# Ethernet.net
KiCad netlist of a schematic drawn in Altium Designer
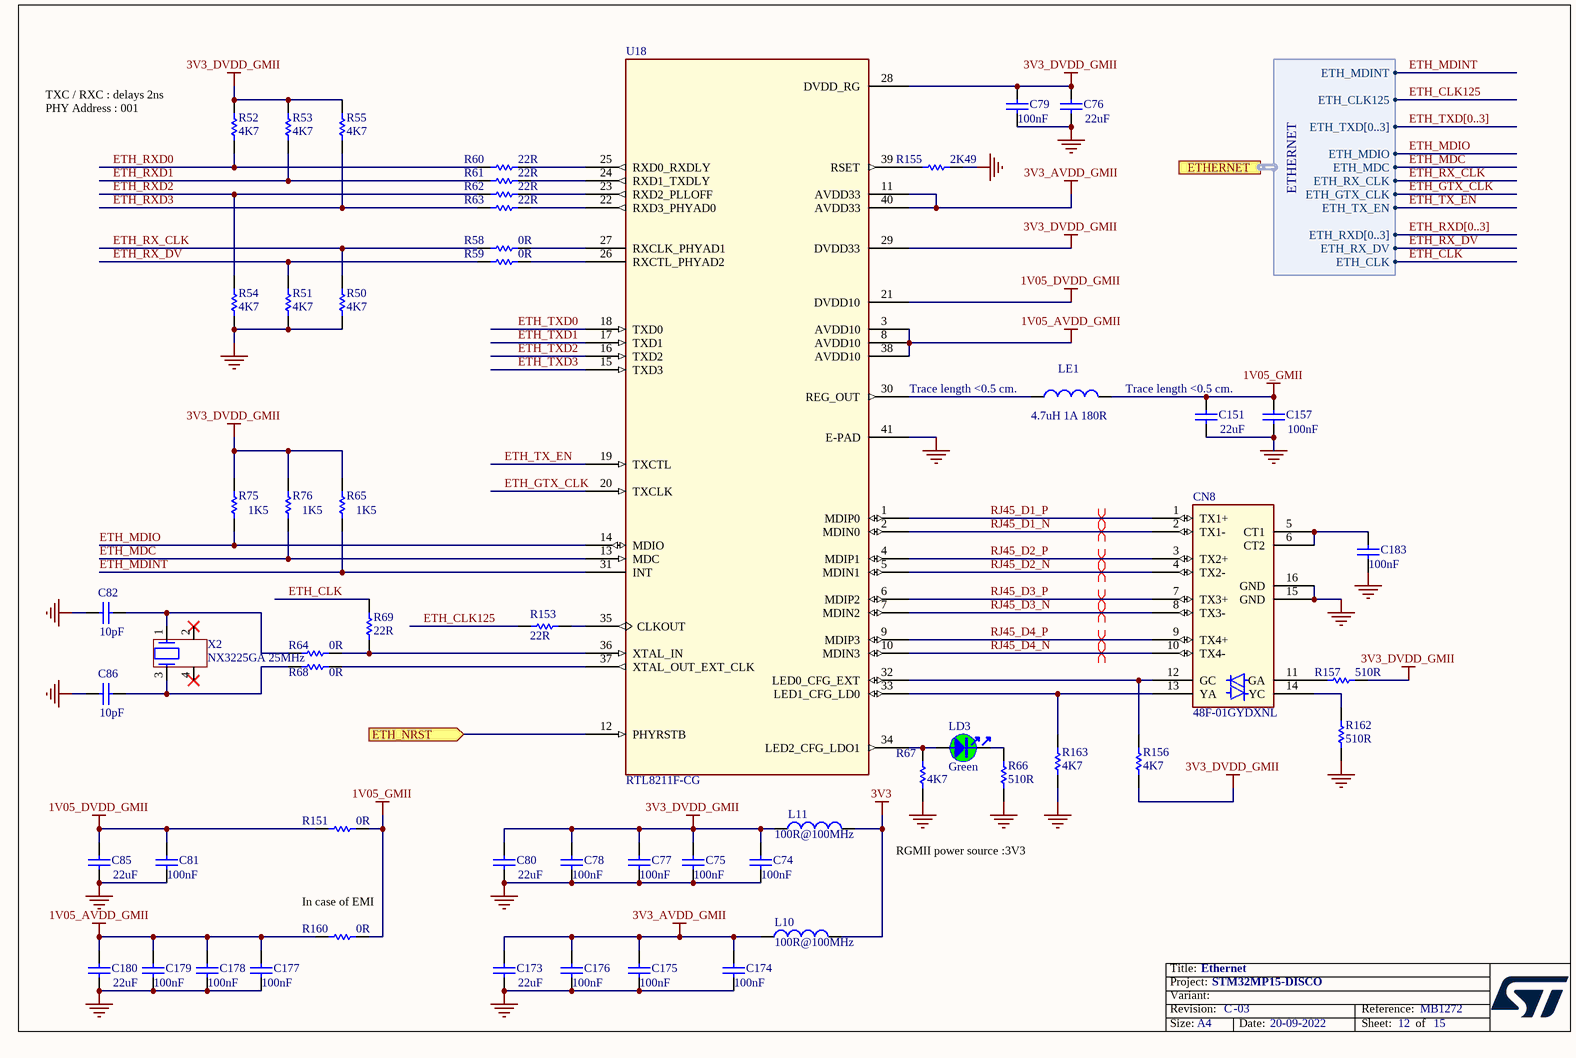
[diagram p0: Ethernet.SchDoc]

(export (version "E")
  (design (tool "Eeschema 10.0.6"))
  (components
    (comp (ref "C74")
      (value "100nF")
      (footprint "C0402")
      (description "Capacitor,100nF,16V,X7R,10%,0402")
      (fields
        (field (name "INTERNAL_PART_NUMBER") "MCD-00006")
        (field (name "MANUFACTURER_PART_NUMBER") "CC0402KRX7R7BB104")
        (field (name "PROVIDED_BY") "SUBCO")
      )
      (libsource (lib "MCD_PARTS_database") (part "Capacitor"))
    )
    (comp (ref "C75")
      (value "100nF")
      (footprint "C0402")
      (description "Capacitor,100nF,16V,X7R,10%,0402")
      (fields
        (field (name "INTERNAL_PART_NUMBER") "MCD-00006")
        (field (name "MANUFACTURER_PART_NUMBER") "CC0402KRX7R7BB104")
        (field (name "PROVIDED_BY") "SUBCO")
      )
      (libsource (lib "MCD_PARTS_database") (part "Capacitor"))
    )
    (comp (ref "C76")
      (value "22uF")
      (footprint "C0603")
      (description "Capacitor,22uF,6V3,X5R,20%,0603")
      (fields
        (field (name "INTERNAL_PART_NUMBER") "MCD-00100")
        (field (name "MANUFACTURER_PART_NUMBER") "GRM188R60J226MEA0J")
        (field (name "PROVIDED_BY") "SUBCO")
      )
      (libsource (lib "MCD_PARTS_database") (part "Capacitor"))
    )
    (comp (ref "C77")
      (value "100nF")
      (footprint "C0402")
      (description "Capacitor,100nF,16V,X7R,10%,0402")
      (fields
        (field (name "INTERNAL_PART_NUMBER") "MCD-00006")
        (field (name "MANUFACTURER_PART_NUMBER") "CC0402KRX7R7BB104")
        (field (name "PROVIDED_BY") "SUBCO")
      )
      (libsource (lib "MCD_PARTS_database") (part "Capacitor"))
    )
    (comp (ref "C78")
      (value "100nF")
      (footprint "C0402")
      (description "Capacitor,100nF,16V,X7R,10%,0402")
      (fields
        (field (name "INTERNAL_PART_NUMBER") "MCD-00006")
        (field (name "MANUFACTURER_PART_NUMBER") "CC0402KRX7R7BB104")
        (field (name "PROVIDED_BY") "SUBCO")
      )
      (libsource (lib "MCD_PARTS_database") (part "Capacitor"))
    )
    (comp (ref "C79")
      (value "100nF")
      (footprint "C0402")
      (description "Capacitor,100nF,16V,X7R,10%,0402")
      (fields
        (field (name "INTERNAL_PART_NUMBER") "MCD-00006")
        (field (name "MANUFACTURER_PART_NUMBER") "CC0402KRX7R7BB104")
        (field (name "PROVIDED_BY") "SUBCO")
      )
      (libsource (lib "MCD_PARTS_database") (part "Capacitor"))
    )
    (comp (ref "C80")
      (value "22uF")
      (footprint "C0603")
      (description "Capacitor,22uF,6V3,X5R,20%,0603")
      (fields
        (field (name "INTERNAL_PART_NUMBER") "MCD-00100")
        (field (name "MANUFACTURER_PART_NUMBER") "GRM188R60J226MEA0J")
        (field (name "PROVIDED_BY") "SUBCO")
      )
      (libsource (lib "MCD_PARTS_database") (part "Capacitor"))
    )
    (comp (ref "C81")
      (value "100nF")
      (footprint "C0402")
      (description "Capacitor,100nF,16V,X7R,10%,0402")
      (fields
        (field (name "INTERNAL_PART_NUMBER") "MCD-00006")
        (field (name "MANUFACTURER_PART_NUMBER") "CC0402KRX7R7BB104")
        (field (name "PROVIDED_BY") "SUBCO")
      )
      (libsource (lib "MCD_PARTS_database") (part "Capacitor"))
    )
    (comp (ref "C82")
      (value "10pF")
      (footprint "C0402")
      (description "Capacitor,10pF,50V,NPO,5%,0402")
      (fields
        (field (name "INTERNAL_PART_NUMBER") "MCD-00015")
        (field (name "MANUFACTURER_PART_NUMBER") "CC0402JRNPO9BN100")
        (field (name "PROVIDED_BY") "SUBCO")
      )
      (libsource (lib "MCD_PARTS_database") (part "Capacitor"))
    )
    (comp (ref "C85")
      (value "22uF")
      (footprint "C0603")
      (description "Capacitor,22uF,6V3,X5R,20%,0603")
      (fields
        (field (name "INTERNAL_PART_NUMBER") "MCD-00100")
        (field (name "MANUFACTURER_PART_NUMBER") "GRM188R60J226MEA0J")
        (field (name "PROVIDED_BY") "SUBCO")
      )
      (libsource (lib "MCD_PARTS_database") (part "Capacitor"))
    )
    (comp (ref "C86")
      (value "10pF")
      (footprint "C0402")
      (description "Capacitor,10pF,50V,NPO,5%,0402")
      (fields
        (field (name "INTERNAL_PART_NUMBER") "MCD-00015")
        (field (name "MANUFACTURER_PART_NUMBER") "CC0402JRNPO9BN100")
        (field (name "PROVIDED_BY") "SUBCO")
      )
      (libsource (lib "MCD_PARTS_database") (part "Capacitor"))
    )
    (comp (ref "C151")
      (value "22uF")
      (footprint "C0603")
      (description "Capacitor,22uF,6V3,X5R,20%,0603")
      (fields
        (field (name "INTERNAL_PART_NUMBER") "MCD-00100")
        (field (name "MANUFACTURER_PART_NUMBER") "GRM188R60J226MEA0J")
        (field (name "PROVIDED_BY") "SUBCO")
      )
      (libsource (lib "MCD_PARTS_database") (part "Capacitor"))
    )
    (comp (ref "C157")
      (value "100nF")
      (footprint "C0402")
      (description "Capacitor,100nF,16V,X7R,10%,0402")
      (fields
        (field (name "INTERNAL_PART_NUMBER") "MCD-00006")
        (field (name "MANUFACTURER_PART_NUMBER") "CC0402KRX7R7BB104")
        (field (name "PROVIDED_BY") "SUBCO")
      )
      (libsource (lib "MCD_PARTS_database") (part "Capacitor"))
    )
    (comp (ref "C173")
      (value "22uF")
      (footprint "C0603")
      (description "Capacitor,22uF,6V3,X5R,20%,0603")
      (fields
        (field (name "INTERNAL_PART_NUMBER") "MCD-00100")
        (field (name "MANUFACTURER_PART_NUMBER") "GRM188R60J226MEA0J")
        (field (name "PROVIDED_BY") "SUBCO")
      )
      (libsource (lib "MCD_PARTS_database") (part "Capacitor"))
    )
    (comp (ref "C174")
      (value "100nF")
      (footprint "C0402")
      (description "Capacitor,100nF,16V,X7R,10%,0402")
      (fields
        (field (name "INTERNAL_PART_NUMBER") "MCD-00006")
        (field (name "MANUFACTURER_PART_NUMBER") "CC0402KRX7R7BB104")
        (field (name "PROVIDED_BY") "SUBCO")
      )
      (libsource (lib "MCD_PARTS_database") (part "Capacitor"))
    )
    (comp (ref "C175")
      (value "100nF")
      (footprint "C0402")
      (description "Capacitor,100nF,16V,X7R,10%,0402")
      (fields
        (field (name "INTERNAL_PART_NUMBER") "MCD-00006")
        (field (name "MANUFACTURER_PART_NUMBER") "CC0402KRX7R7BB104")
        (field (name "PROVIDED_BY") "SUBCO")
      )
      (libsource (lib "MCD_PARTS_database") (part "Capacitor"))
    )
    (comp (ref "C176")
      (value "100nF")
      (footprint "C0402")
      (description "Capacitor,100nF,16V,X7R,10%,0402")
      (fields
        (field (name "INTERNAL_PART_NUMBER") "MCD-00006")
        (field (name "MANUFACTURER_PART_NUMBER") "CC0402KRX7R7BB104")
        (field (name "PROVIDED_BY") "SUBCO")
      )
      (libsource (lib "MCD_PARTS_database") (part "Capacitor"))
    )
    (comp (ref "C177")
      (value "100nF")
      (footprint "C0402")
      (description "Capacitor,100nF,16V,X7R,10%,0402")
      (fields
        (field (name "INTERNAL_PART_NUMBER") "MCD-00006")
        (field (name "MANUFACTURER_PART_NUMBER") "CC0402KRX7R7BB104")
        (field (name "PROVIDED_BY") "SUBCO")
      )
      (libsource (lib "MCD_PARTS_database") (part "Capacitor"))
    )
    (comp (ref "C178")
      (value "100nF")
      (footprint "C0402")
      (description "Capacitor,100nF,16V,X7R,10%,0402")
      (fields
        (field (name "INTERNAL_PART_NUMBER") "MCD-00006")
        (field (name "MANUFACTURER_PART_NUMBER") "CC0402KRX7R7BB104")
        (field (name "PROVIDED_BY") "SUBCO")
      )
      (libsource (lib "MCD_PARTS_database") (part "Capacitor"))
    )
    (comp (ref "C179")
      (value "100nF")
      (footprint "C0402")
      (description "Capacitor,100nF,16V,X7R,10%,0402")
      (fields
        (field (name "INTERNAL_PART_NUMBER") "MCD-00006")
        (field (name "MANUFACTURER_PART_NUMBER") "CC0402KRX7R7BB104")
        (field (name "PROVIDED_BY") "SUBCO")
      )
      (libsource (lib "MCD_PARTS_database") (part "Capacitor"))
    )
    (comp (ref "C180")
      (value "22uF")
      (footprint "C0603")
      (description "Capacitor,22uF,6V3,X5R,20%,0603")
      (fields
        (field (name "INTERNAL_PART_NUMBER") "MCD-00100")
        (field (name "MANUFACTURER_PART_NUMBER") "GRM188R60J226MEA0J")
        (field (name "PROVIDED_BY") "SUBCO")
      )
      (libsource (lib "MCD_PARTS_database") (part "Capacitor"))
    )
    (comp (ref "C183")
      (value "100nF")
      (footprint "C0402")
      (description "Capacitor,100nF,16V,X7R,10%,0402")
      (fields
        (field (name "INTERNAL_PART_NUMBER") "MCD-00006")
        (field (name "MANUFACTURER_PART_NUMBER") "CC0402KRX7R7BB104")
        (field (name "PROVIDED_BY") "SUBCO")
      )
      (libsource (lib "MCD_PARTS_database") (part "Capacitor"))
    )
    (comp (ref "CN8")
      (value "48F-01GYDXNL")
      (footprint "CON_RJ45_YD_48F-01GYDXNL_LED-P")
      (description "Connector RJ45 with Gigabit magnetics and LED , led pull down")
      (fields
        (field (name "INTERNAL_PART_NUMBER") "MCD-01129")
        (field (name "MANUFACTURER") "YUAN DEAN SCIENTIFIC")
        (field (name "PROVIDED_BY") "SUBCO")
      )
      (libsource (lib "MCD_PARTS_database") (part "RJ45_48F_01GYDXNL_LPD"))
    )
    (comp (ref "L10")
      (value "100R@100MHz")
      (footprint "FIL_0603_H0P65")
      (description "Ferrite bead 100R 2A 0603")
      (fields
        (field (name "INTERNAL_PART_NUMBER") "MCD-00094")
        (field (name "MANUFACTURER_PART_NUMBER") "BLM18EG101TN1")
        (field (name "PROVIDED_BY") "SUBCO")
      )
      (libsource (lib "MCD_PARTS_database") (part "BEAD"))
    )
    (comp (ref "L11")
      (value "100R@100MHz")
      (footprint "FIL_0603_H0P65")
      (description "Ferrite bead 100R 2A 0603")
      (fields
        (field (name "INTERNAL_PART_NUMBER") "MCD-00094")
        (field (name "MANUFACTURER_PART_NUMBER") "BLM18EG101TN1")
        (field (name "PROVIDED_BY") "SUBCO")
      )
      (libsource (lib "MCD_PARTS_database") (part "BEAD"))
    )
    (comp (ref "LD3")
      (value "Green")
      (footprint "LED_0603_GREEN")
      (description "LED, Green, 2V, 20mA, 0603")
      (fields (field (name "INTERNAL_PART_NUMBER") "MCD-02900") (field (name "MANUFACTURER") "EVERLIGHT"))
      (libsource (lib "MCD_PARTS_database") (part "LED_green"))
    )
    (comp (ref "LE1")
      (value "4.7uH 1A 180R")
      (footprint "L1210_LQH")
      (description "FIXED IND 4.7UH 1A 180 MOHM 30% SMD")
      (fields
        (field (name "INTERNAL_PART_NUMBER") "MCD-00048")
        (field (name "MANUFACTURER_PART_NUMBER") "LQH32PN4R7NN0L")
        (field (name "PROVIDED_BY") "SUBCO")
      )
      (libsource (lib "MCD_PARTS_database") (part "Inductor"))
    )
    (comp (ref "R50")
      (value "4K7")
      (footprint "R0402")
      (description "Resistor,4K7,0402,1%,1/16W")
      (fields
        (field (name "INTERNAL_PART_NUMBER") "MCD-00065")
        (field (name "MANUFACTURER_PART_NUMBER") "RC0402FR-074K7L")
        (field (name "PROVIDED_BY") "SUBCO")
      )
      (libsource (lib "MCD_PARTS_database") (part "Resistor"))
    )
    (comp (ref "R51")
      (value "4K7")
      (footprint "R0402")
      (description "Resistor,4K7,0402,1%,1/16W")
      (fields
        (field (name "INTERNAL_PART_NUMBER") "MCD-00065")
        (field (name "MANUFACTURER_PART_NUMBER") "RC0402FR-074K7L")
        (field (name "PROVIDED_BY") "SUBCO")
      )
      (libsource (lib "MCD_PARTS_database") (part "Resistor"))
    )
    (comp (ref "R52")
      (value "4K7")
      (footprint "R0402")
      (description "Resistor,4K7,0402,1%,1/16W")
      (fields
        (field (name "INTERNAL_PART_NUMBER") "MCD-00065")
        (field (name "MANUFACTURER_PART_NUMBER") "RC0402FR-074K7L")
        (field (name "PROVIDED_BY") "SUBCO")
      )
      (libsource (lib "MCD_PARTS_database") (part "Resistor"))
    )
    (comp (ref "R53")
      (value "4K7")
      (footprint "R0402")
      (description "Resistor,4K7,0402,1%,1/16W")
      (fields
        (field (name "INTERNAL_PART_NUMBER") "MCD-00065")
        (field (name "MANUFACTURER_PART_NUMBER") "RC0402FR-074K7L")
        (field (name "PROVIDED_BY") "SUBCO")
      )
      (libsource (lib "MCD_PARTS_database") (part "Resistor"))
    )
    (comp (ref "R54")
      (value "4K7")
      (footprint "R0402")
      (description "Resistor,4K7,0402,1%,1/16W")
      (fields
        (field (name "INTERNAL_PART_NUMBER") "MCD-00065")
        (field (name "MANUFACTURER_PART_NUMBER") "RC0402FR-074K7L")
        (field (name "PROVIDED_BY") "SUBCO")
      )
      (libsource (lib "MCD_PARTS_database") (part "Resistor"))
    )
    (comp (ref "R55")
      (value "4K7")
      (footprint "R0402")
      (description "Resistor,4K7,0402,1%,1/16W")
      (fields
        (field (name "INTERNAL_PART_NUMBER") "MCD-00065")
        (field (name "MANUFACTURER_PART_NUMBER") "RC0402FR-074K7L")
        (field (name "PROVIDED_BY") "SUBCO")
      )
      (libsource (lib "MCD_PARTS_database") (part "Resistor"))
    )
    (comp (ref "R58")
      (value "0R")
      (footprint "R0402")
      (description "Resistor,0R,0402,5%,1/16W")
      (fields
        (field (name "INTERNAL_PART_NUMBER") "MCD-00052")
        (field (name "MANUFACTURER_PART_NUMBER") "RC0402JR-070RL")
        (field (name "PROVIDED_BY") "SUBCO")
      )
      (libsource (lib "MCD_PARTS_database") (part "Resistor"))
    )
    (comp (ref "R59")
      (value "0R")
      (footprint "R0402")
      (description "Resistor,0R,0402,5%,1/16W")
      (fields
        (field (name "INTERNAL_PART_NUMBER") "MCD-00052")
        (field (name "MANUFACTURER_PART_NUMBER") "RC0402JR-070RL")
        (field (name "PROVIDED_BY") "SUBCO")
      )
      (libsource (lib "MCD_PARTS_database") (part "Resistor"))
    )
    (comp (ref "R60")
      (value "22R")
      (footprint "R0402")
      (description "Resistor,22R,0402,1%,1/16W")
      (fields
        (field (name "INTERNAL_PART_NUMBER") "MCD-00189")
        (field (name "MANUFACTURER_PART_NUMBER") "RC0402FR-0722RL")
        (field (name "PROVIDED_BY") "SUBCO")
      )
      (libsource (lib "MCD_PARTS_database") (part "Resistor"))
    )
    (comp (ref "R61")
      (value "22R")
      (footprint "R0402")
      (description "Resistor,22R,0402,1%,1/16W")
      (fields
        (field (name "INTERNAL_PART_NUMBER") "MCD-00189")
        (field (name "MANUFACTURER_PART_NUMBER") "RC0402FR-0722RL")
        (field (name "PROVIDED_BY") "SUBCO")
      )
      (libsource (lib "MCD_PARTS_database") (part "Resistor"))
    )
    (comp (ref "R62")
      (value "22R")
      (footprint "R0402")
      (description "Resistor,22R,0402,1%,1/16W")
      (fields
        (field (name "INTERNAL_PART_NUMBER") "MCD-00189")
        (field (name "MANUFACTURER_PART_NUMBER") "RC0402FR-0722RL")
        (field (name "PROVIDED_BY") "SUBCO")
      )
      (libsource (lib "MCD_PARTS_database") (part "Resistor"))
    )
    (comp (ref "R63")
      (value "22R")
      (footprint "R0402")
      (description "Resistor,22R,0402,1%,1/16W")
      (fields
        (field (name "INTERNAL_PART_NUMBER") "MCD-00189")
        (field (name "MANUFACTURER_PART_NUMBER") "RC0402FR-0722RL")
        (field (name "PROVIDED_BY") "SUBCO")
      )
      (libsource (lib "MCD_PARTS_database") (part "Resistor"))
    )
    (comp (ref "R64")
      (value "0R")
      (footprint "R0402")
      (description "Resistor,0R,0402,5%,1/16W")
      (fields
        (field (name "INTERNAL_PART_NUMBER") "MCD-00052")
        (field (name "MANUFACTURER_PART_NUMBER") "RC0402JR-070RL")
        (field (name "PROVIDED_BY") "SUBCO")
      )
      (libsource (lib "MCD_PARTS_database") (part "Resistor"))
    )
    (comp (ref "R65")
      (value "1K5")
      (footprint "R0402")
      (description "Resistor,1K5,0402,1%,1/16W")
      (fields
        (field (name "INTERNAL_PART_NUMBER") "MCD-00068")
        (field (name "MANUFACTURER_PART_NUMBER") "RC0402FR-071K5L")
        (field (name "PROVIDED_BY") "SUBCO")
      )
      (libsource (lib "MCD_PARTS_database") (part "Resistor"))
    )
    (comp (ref "R66")
      (value "510R")
      (footprint "R0402")
      (description "Resistor,510R,0402,1%,1/16W")
      (fields
        (field (name "INTERNAL_PART_NUMBER") "MCD-00064")
        (field (name "MANUFACTURER_PART_NUMBER") "RC0402FR-07510RL")
        (field (name "PROVIDED_BY") "SUBCO")
      )
      (libsource (lib "MCD_PARTS_database") (part "Resistor"))
    )
    (comp (ref "R67")
      (value "4K7")
      (footprint "R0402")
      (description "Resistor,4K7,0402,1%,1/16W")
      (fields
        (field (name "INTERNAL_PART_NUMBER") "MCD-00065")
        (field (name "MANUFACTURER_PART_NUMBER") "RC0402FR-074K7L")
        (field (name "PROVIDED_BY") "SUBCO")
      )
      (libsource (lib "MCD_PARTS_database") (part "Resistor"))
    )
    (comp (ref "R68")
      (value "0R")
      (footprint "R0402")
      (description "Resistor,0R,0402,5%,1/16W")
      (fields
        (field (name "INTERNAL_PART_NUMBER") "MCD-00052")
        (field (name "MANUFACTURER_PART_NUMBER") "RC0402JR-070RL")
        (field (name "PROVIDED_BY") "SUBCO")
      )
      (libsource (lib "MCD_PARTS_database") (part "Resistor"))
    )
    (comp (ref "R69")
      (value "22R")
      (footprint "R0402")
      (description "Resistor,22R,0402,1%,1/16W")
      (fields
        (field (name "INTERNAL_PART_NUMBER") "MCD-00189")
        (field (name "MANUFACTURER_PART_NUMBER") "RC0402FR-0722RL")
        (field (name "PROVIDED_BY") "SUBCO")
      )
      (libsource (lib "MCD_PARTS_database") (part "Resistor"))
    )
    (comp (ref "R75")
      (value "1K5")
      (footprint "R0402")
      (description "Resistor,1K5,0402,1%,1/16W")
      (fields
        (field (name "INTERNAL_PART_NUMBER") "MCD-00068")
        (field (name "MANUFACTURER_PART_NUMBER") "RC0402FR-071K5L")
        (field (name "PROVIDED_BY") "SUBCO")
      )
      (libsource (lib "MCD_PARTS_database") (part "Resistor"))
    )
    (comp (ref "R76")
      (value "1K5")
      (footprint "R0402")
      (description "Resistor,1K5,0402,1%,1/16W")
      (fields
        (field (name "INTERNAL_PART_NUMBER") "MCD-00068")
        (field (name "MANUFACTURER_PART_NUMBER") "RC0402FR-071K5L")
        (field (name "PROVIDED_BY") "SUBCO")
      )
      (libsource (lib "MCD_PARTS_database") (part "Resistor"))
    )
    (comp (ref "R151")
      (value "0R")
      (footprint "R0603")
      (description "Resistor,0R,0603,5%,1/10W")
      (fields
        (field (name "INTERNAL_PART_NUMBER") "MCD-00056")
        (field (name "MANUFACTURER_PART_NUMBER") "RC0603JR-070RL")
        (field (name "PROVIDED_BY") "SUBCO")
      )
      (libsource (lib "MCD_PARTS_database") (part "Resistor"))
    )
    (comp (ref "R153")
      (value "22R")
      (footprint "R0402")
      (description "Resistor,22R,0402,1%,1/16W")
      (fields
        (field (name "INTERNAL_PART_NUMBER") "MCD-00189")
        (field (name "MANUFACTURER_PART_NUMBER") "RC0402FR-0722RL")
        (field (name "PROVIDED_BY") "SUBCO")
      )
      (libsource (lib "MCD_PARTS_database") (part "Resistor"))
    )
    (comp (ref "R155")
      (value "2K49")
      (footprint "R0402")
      (description "Resistor,2K49,0402,1%,1/16W")
      (fields
        (field (name "INTERNAL_PART_NUMBER") "MCD-00183")
        (field (name "MANUFACTURER_PART_NUMBER") "RC0402FR-072K49L")
        (field (name "PROVIDED_BY") "SUBCO")
      )
      (libsource (lib "MCD_PARTS_database") (part "Resistor"))
    )
    (comp (ref "R156")
      (value "4K7")
      (footprint "R0402")
      (description "Resistor,4K7,0402,1%,1/16W")
      (fields
        (field (name "INTERNAL_PART_NUMBER") "MCD-00065")
        (field (name "MANUFACTURER_PART_NUMBER") "RC0402FR-074K7L")
        (field (name "PROVIDED_BY") "SUBCO")
      )
      (libsource (lib "MCD_PARTS_database") (part "Resistor"))
    )
    (comp (ref "R157")
      (value "510R")
      (footprint "R0402")
      (description "Resistor,510R,0402,1%,1/16W")
      (fields
        (field (name "INTERNAL_PART_NUMBER") "MCD-00064")
        (field (name "MANUFACTURER_PART_NUMBER") "RC0402FR-07510RL")
        (field (name "PROVIDED_BY") "SUBCO")
      )
      (libsource (lib "MCD_PARTS_database") (part "Resistor"))
    )
    (comp (ref "R160")
      (value "0R")
      (footprint "R0603")
      (description "Resistor,0R,0603,5%,1/10W")
      (fields
        (field (name "INTERNAL_PART_NUMBER") "MCD-00056")
        (field (name "MANUFACTURER_PART_NUMBER") "RC0603JR-070RL")
        (field (name "PROVIDED_BY") "SUBCO")
      )
      (libsource (lib "MCD_PARTS_database") (part "Resistor"))
    )
    (comp (ref "R162")
      (value "510R")
      (footprint "R0402")
      (description "Resistor,510R,0402,1%,1/16W")
      (fields
        (field (name "INTERNAL_PART_NUMBER") "MCD-00064")
        (field (name "MANUFACTURER_PART_NUMBER") "RC0402FR-07510RL")
        (field (name "PROVIDED_BY") "SUBCO")
      )
      (libsource (lib "MCD_PARTS_database") (part "Resistor"))
    )
    (comp (ref "R163")
      (value "4K7")
      (footprint "R0402")
      (description "Resistor,4K7,0402,1%,1/16W")
      (fields
        (field (name "INTERNAL_PART_NUMBER") "MCD-00065")
        (field (name "MANUFACTURER_PART_NUMBER") "RC0402FR-074K7L")
        (field (name "PROVIDED_BY") "SUBCO")
      )
      (libsource (lib "MCD_PARTS_database") (part "Resistor"))
    )
    (comp (ref "U18")
      (value "RTL8211F-CG")
      (footprint "ICC_QFN40-EPAD_5X5_P040")
      (description "10/100/1000M GIGABIT Ethernet Transceiver, QFN40 , SMPS version")
      (fields
        (field (name "INTERNAL_PART_NUMBER") "MCD-01130")
        (field (name "MANUFACTURER") "REALTEK")
        (field (name "PROVIDED_BY") "SUBCO")
      )
      (libsource (lib "MCD_PARTS_database") (part "RTL8211F-CG"))
    )
    (comp (ref "X2")
      (value "NX3225GA 25MHz")
      (footprint "CRY_NX3225HA_4P")
      (description "Crystal 25Mhz, 10pF, -+50PPM, SMD")
      (fields
        (field (name "INTERNAL_PART_NUMBER") "MCD-01463")
        (field (name "MANUFACTURER_PART_NUMBER") "NX3225GA 25MHz EXS00A-CG06750")
        (field (name "PROVIDED_BY") "SUBCO")
      )
      (libsource (lib "MCD_PARTS_database") (part "XTAL_4_PINS"))
    )
  )
  (nets
    (net (code "2") (name "/ETH_CLK") (class "Default")
      (node (ref "R69") (pin "2") (pinfunction "2_2") (pintype "passive"))
    )
    (net (code "3") (name "/ETH_CLK125") (class "Default")
      (node (ref "R153") (pin "1") (pinfunction "1_1") (pintype "passive"))
    )
    (net (code "4") (name "/ETH_GTX_CLK") (class "Default")
      (node (ref "U18") (pin "20") (pinfunction "TXCLK_20") (pintype "input"))
    )
    (net (code "5") (name "/ETH_MDC") (class "Default")
      (node (ref "R76") (pin "1") (pinfunction "1_1") (pintype "passive"))
      (node (ref "U18") (pin "13") (pinfunction "MDC_13") (pintype "input"))
    )
    (net (code "6") (name "/ETH_MDINT") (class "Default")
      (node (ref "R65") (pin "1") (pinfunction "1_1") (pintype "passive"))
      (node (ref "U18") (pin "31") (pinfunction "INT_31") (pintype "passive"))
    )
    (net (code "7") (name "/ETH_MDIO") (class "Default")
      (node (ref "R75") (pin "1") (pinfunction "1_1") (pintype "passive"))
      (node (ref "U18") (pin "14") (pinfunction "MDIO_14") (pintype "bidirectional"))
    )
    (net (code "8") (name "/ETH_NRST") (class "Default")
      (node (ref "U18") (pin "12") (pinfunction "PHYRSTB_12") (pintype "input"))
    )
    (net (code "9") (name "/ETH_RXD0") (class "Default")
      (node (ref "R52") (pin "1") (pinfunction "1_1") (pintype "passive"))
      (node (ref "R60") (pin "1") (pinfunction "1_1") (pintype "passive"))
    )
    (net (code "10") (name "/ETH_RXD1") (class "Default")
      (node (ref "R53") (pin "1") (pinfunction "1_1") (pintype "passive"))
      (node (ref "R61") (pin "1") (pinfunction "1_1") (pintype "passive"))
    )
    (net (code "11") (name "/ETH_RXD2") (class "Default")
      (node (ref "R54") (pin "2") (pinfunction "2_2") (pintype "passive"))
      (node (ref "R62") (pin "1") (pinfunction "1_1") (pintype "passive"))
    )
    (net (code "12") (name "/ETH_RXD3") (class "Default")
      (node (ref "R55") (pin "1") (pinfunction "1_1") (pintype "passive"))
      (node (ref "R63") (pin "1") (pinfunction "1_1") (pintype "passive"))
    )
    (net (code "14") (name "/ETH_RX_CLK") (class "Default")
      (node (ref "R50") (pin "2") (pinfunction "2_2") (pintype "passive"))
      (node (ref "R58") (pin "1") (pinfunction "1_1") (pintype "passive"))
    )
    (net (code "15") (name "/ETH_RX_DV") (class "Default")
      (node (ref "R51") (pin "2") (pinfunction "2_2") (pintype "passive"))
      (node (ref "R59") (pin "1") (pinfunction "1_1") (pintype "passive"))
    )
    (net (code "16") (name "/ETH_TXD0") (class "Default")
      (node (ref "U18") (pin "18") (pinfunction "TXD0_18") (pintype "input"))
    )
    (net (code "17") (name "/ETH_TXD1") (class "Default")
      (node (ref "U18") (pin "17") (pinfunction "TXD1_17") (pintype "input"))
    )
    (net (code "18") (name "/ETH_TXD2") (class "Default")
      (node (ref "U18") (pin "16") (pinfunction "TXD2_16") (pintype "input"))
    )
    (net (code "19") (name "/ETH_TXD3") (class "Default")
      (node (ref "U18") (pin "15") (pinfunction "TXD3_15") (pintype "input"))
    )
    (net (code "21") (name "/ETH_TX_EN") (class "Default")
      (node (ref "U18") (pin "19") (pinfunction "TXCTL_19") (pintype "input"))
    )
    (net (code "22") (name "/RJ45_D1_N") (class "Default")
      (node (ref "CN8") (pin "2") (pinfunction "TX1-_2") (pintype "bidirectional"))
      (node (ref "U18") (pin "2") (pinfunction "MDIN0_2") (pintype "bidirectional"))
    )
    (net (code "23") (name "/RJ45_D1_P") (class "Default")
      (node (ref "CN8") (pin "1") (pinfunction "TX1+_1") (pintype "bidirectional"))
      (node (ref "U18") (pin "1") (pinfunction "MDIP0_1") (pintype "bidirectional"))
    )
    (net (code "24") (name "/RJ45_D2_N") (class "Default")
      (node (ref "CN8") (pin "4") (pinfunction "TX2-_4") (pintype "bidirectional"))
      (node (ref "U18") (pin "5") (pinfunction "MDIN1_5") (pintype "bidirectional"))
    )
    (net (code "25") (name "/RJ45_D2_P") (class "Default")
      (node (ref "CN8") (pin "3") (pinfunction "TX2+_3") (pintype "bidirectional"))
      (node (ref "U18") (pin "4") (pinfunction "MDIP1_4") (pintype "bidirectional"))
    )
    (net (code "26") (name "/RJ45_D3_N") (class "Default")
      (node (ref "CN8") (pin "8") (pinfunction "TX3-_8") (pintype "bidirectional"))
      (node (ref "U18") (pin "7") (pinfunction "MDIN2_7") (pintype "bidirectional"))
    )
    (net (code "27") (name "/RJ45_D3_P") (class "Default")
      (node (ref "CN8") (pin "7") (pinfunction "TX3+_7") (pintype "bidirectional"))
      (node (ref "U18") (pin "6") (pinfunction "MDIP2_6") (pintype "bidirectional"))
    )
    (net (code "28") (name "/RJ45_D4_N") (class "Default")
      (node (ref "CN8") (pin "10") (pinfunction "TX4-_10") (pintype "bidirectional"))
      (node (ref "U18") (pin "10") (pinfunction "MDIN3_10") (pintype "bidirectional"))
    )
    (net (code "29") (name "/RJ45_D4_P") (class "Default")
      (node (ref "CN8") (pin "9") (pinfunction "TX4+_9") (pintype "bidirectional"))
      (node (ref "U18") (pin "9") (pinfunction "MDIP3_9") (pintype "bidirectional"))
    )
    (net (code "31") (name "1V05_AVDD_GMII") (class "Default")
      (node (ref "C177") (pin "2") (pinfunction "2_2") (pintype "passive"))
      (node (ref "C178") (pin "2") (pinfunction "2_2") (pintype "passive"))
      (node (ref "C179") (pin "2") (pinfunction "2_2") (pintype "passive"))
      (node (ref "C180") (pin "2") (pinfunction "2_2") (pintype "passive"))
      (node (ref "R160") (pin "1") (pinfunction "1_1") (pintype "passive"))
      (node (ref "U18") (pin "3") (pinfunction "AVDD10_3") (pintype "power_in"))
      (node (ref "U18") (pin "38") (pinfunction "AVDD10_38") (pintype "power_in"))
      (node (ref "U18") (pin "8") (pinfunction "AVDD10_8") (pintype "power_in"))
    )
    (net (code "32") (name "1V05_DVDD_GMII") (class "Default")
      (node (ref "C81") (pin "2") (pinfunction "2_2") (pintype "passive"))
      (node (ref "C85") (pin "2") (pinfunction "2_2") (pintype "passive"))
      (node (ref "R151") (pin "1") (pinfunction "1_1") (pintype "passive"))
      (node (ref "U18") (pin "21") (pinfunction "DVDD10_21") (pintype "power_in"))
    )
    (net (code "33") (name "1V05_GMII") (class "Default")
      (node (ref "C151") (pin "2") (pinfunction "2_2") (pintype "passive"))
      (node (ref "C157") (pin "2") (pinfunction "2_2") (pintype "passive"))
      (node (ref "LE1") (pin "2") (pinfunction "2_2") (pintype "passive"))
      (node (ref "R151") (pin "2") (pinfunction "2_2") (pintype "passive"))
      (node (ref "R160") (pin "2") (pinfunction "2_2") (pintype "passive"))
    )
    (net (code "34") (name "3V3") (class "Default")
      (node (ref "L10") (pin "2") (pinfunction "2_2") (pintype "passive"))
      (node (ref "L11") (pin "2") (pinfunction "2_2") (pintype "passive"))
    )
    (net (code "35") (name "3V3_AVDD_GMII") (class "Default")
      (node (ref "C173") (pin "2") (pinfunction "2_2") (pintype "passive"))
      (node (ref "C174") (pin "2") (pinfunction "2_2") (pintype "passive"))
      (node (ref "C175") (pin "2") (pinfunction "2_2") (pintype "passive"))
      (node (ref "C176") (pin "2") (pinfunction "2_2") (pintype "passive"))
      (node (ref "L10") (pin "1") (pinfunction "1_1") (pintype "passive"))
      (node (ref "U18") (pin "11") (pinfunction "AVDD33_11") (pintype "power_in"))
      (node (ref "U18") (pin "40") (pinfunction "AVDD33_40") (pintype "power_in"))
    )
    (net (code "36") (name "3V3_DVDD_GMII") (class "Default")
      (node (ref "C74") (pin "2") (pinfunction "2_2") (pintype "passive"))
      (node (ref "C75") (pin "2") (pinfunction "2_2") (pintype "passive"))
      (node (ref "C76") (pin "1") (pinfunction "1_1") (pintype "passive"))
      (node (ref "C77") (pin "2") (pinfunction "2_2") (pintype "passive"))
      (node (ref "C78") (pin "2") (pinfunction "2_2") (pintype "passive"))
      (node (ref "C79") (pin "2") (pinfunction "2_2") (pintype "passive"))
      (node (ref "C80") (pin "2") (pinfunction "2_2") (pintype "passive"))
      (node (ref "L11") (pin "1") (pinfunction "1_1") (pintype "passive"))
      (node (ref "R156") (pin "1") (pinfunction "1_1") (pintype "passive"))
      (node (ref "R157") (pin "2") (pinfunction "2_2") (pintype "passive"))
      (node (ref "R52") (pin "2") (pinfunction "2_2") (pintype "passive"))
      (node (ref "R53") (pin "2") (pinfunction "2_2") (pintype "passive"))
      (node (ref "R55") (pin "2") (pinfunction "2_2") (pintype "passive"))
      (node (ref "R65") (pin "2") (pinfunction "2_2") (pintype "passive"))
      (node (ref "R75") (pin "2") (pinfunction "2_2") (pintype "passive"))
      (node (ref "R76") (pin "2") (pinfunction "2_2") (pintype "passive"))
      (node (ref "U18") (pin "28") (pinfunction "DVDD_RG_28") (pintype "power_in"))
      (node (ref "U18") (pin "29") (pinfunction "DVDD33_29") (pintype "power_in"))
    )
    (net (code "37") (name "GND") (class "Default")
      (node (ref "C151") (pin "1") (pinfunction "1_1") (pintype "passive"))
      (node (ref "C157") (pin "1") (pinfunction "1_1") (pintype "passive"))
      (node (ref "C173") (pin "1") (pinfunction "1_1") (pintype "passive"))
      (node (ref "C174") (pin "1") (pinfunction "1_1") (pintype "passive"))
      (node (ref "C175") (pin "1") (pinfunction "1_1") (pintype "passive"))
      (node (ref "C176") (pin "1") (pinfunction "1_1") (pintype "passive"))
      (node (ref "C177") (pin "1") (pinfunction "1_1") (pintype "passive"))
      (node (ref "C178") (pin "1") (pinfunction "1_1") (pintype "passive"))
      (node (ref "C179") (pin "1") (pinfunction "1_1") (pintype "passive"))
      (node (ref "C180") (pin "1") (pinfunction "1_1") (pintype "passive"))
      (node (ref "C183") (pin "1") (pinfunction "1_1") (pintype "passive"))
      (node (ref "C74") (pin "1") (pinfunction "1_1") (pintype "passive"))
      (node (ref "C75") (pin "1") (pinfunction "1_1") (pintype "passive"))
      (node (ref "C76") (pin "2") (pinfunction "2_2") (pintype "passive"))
      (node (ref "C77") (pin "1") (pinfunction "1_1") (pintype "passive"))
      (node (ref "C78") (pin "1") (pinfunction "1_1") (pintype "passive"))
      (node (ref "C79") (pin "1") (pinfunction "1_1") (pintype "passive"))
      (node (ref "C80") (pin "1") (pinfunction "1_1") (pintype "passive"))
      (node (ref "C81") (pin "1") (pinfunction "1_1") (pintype "passive"))
      (node (ref "C82") (pin "1") (pinfunction "1_1") (pintype "passive"))
      (node (ref "C85") (pin "1") (pinfunction "1_1") (pintype "passive"))
      (node (ref "C86") (pin "1") (pinfunction "1_1") (pintype "passive"))
      (node (ref "CN8") (pin "15") (pinfunction "GND_15") (pintype "power_in"))
      (node (ref "CN8") (pin "16") (pinfunction "GND_16") (pintype "power_in"))
      (node (ref "R155") (pin "2") (pinfunction "2_2") (pintype "passive"))
      (node (ref "R162") (pin "1") (pinfunction "1_1") (pintype "passive"))
      (node (ref "R163") (pin "1") (pinfunction "1_1") (pintype "passive"))
      (node (ref "R50") (pin "1") (pinfunction "1_1") (pintype "passive"))
      (node (ref "R51") (pin "1") (pinfunction "1_1") (pintype "passive"))
      (node (ref "R54") (pin "1") (pinfunction "1_1") (pintype "passive"))
      (node (ref "R66") (pin "1") (pinfunction "1_1") (pintype "passive"))
      (node (ref "R67") (pin "1") (pinfunction "1_1") (pintype "passive"))
      (node (ref "U18") (pin "41") (pinfunction "E-PAD_41") (pintype "power_in"))
    )
    (net (code "38") (name "Net-(C82-Pad2)") (class "Default")
      (node (ref "C82") (pin "2") (pinfunction "2_2") (pintype "passive"))
      (node (ref "R64") (pin "1") (pinfunction "1_1") (pintype "passive"))
      (node (ref "X2") (pin "1") (pinfunction "1_1") (pintype "passive"))
    )
    (net (code "39") (name "Net-(C86-Pad2)") (class "Default")
      (node (ref "C86") (pin "2") (pinfunction "2_2") (pintype "passive"))
      (node (ref "R68") (pin "1") (pinfunction "1_1") (pintype "passive"))
      (node (ref "X2") (pin "3") (pinfunction "3_3") (pintype "passive"))
    )
    (net (code "40") (name "Net-(CN8-CT1)") (class "Default")
      (node (ref "C183") (pin "2") (pinfunction "2_2") (pintype "passive"))
      (node (ref "CN8") (pin "5") (pinfunction "CT1_5") (pintype "passive"))
      (node (ref "CN8") (pin "6") (pinfunction "CT2_6") (pintype "passive"))
    )
    (net (code "41") (name "Net-(CN8-GA)") (class "Default")
      (node (ref "CN8") (pin "11") (pinfunction "GA_11") (pintype "passive"))
      (node (ref "R157") (pin "1") (pinfunction "1_1") (pintype "passive"))
    )
    (net (code "42") (name "Net-(CN8-GC)") (class "Default")
      (node (ref "CN8") (pin "12") (pinfunction "GC_12") (pintype "passive"))
      (node (ref "R156") (pin "2") (pinfunction "2_2") (pintype "passive"))
      (node (ref "U18") (pin "32") (pinfunction "LED0_CFG_EXT_32") (pintype "bidirectional"))
    )
    (net (code "43") (name "Net-(CN8-YA)") (class "Default")
      (node (ref "CN8") (pin "13") (pinfunction "YA_13") (pintype "passive"))
      (node (ref "R163") (pin "2") (pinfunction "2_2") (pintype "passive"))
      (node (ref "U18") (pin "33") (pinfunction "LED1_CFG_LD0_33") (pintype "bidirectional"))
    )
    (net (code "44") (name "Net-(CN8-YC)") (class "Default")
      (node (ref "CN8") (pin "14") (pinfunction "YC_14") (pintype "passive"))
      (node (ref "R162") (pin "2") (pinfunction "2_2") (pintype "passive"))
    )
    (net (code "45") (name "Net-(LD3-Pad2)") (class "Default")
      (node (ref "LD3") (pin "2") (pintype "passive"))
      (node (ref "R66") (pin "2") (pinfunction "2_2") (pintype "passive"))
    )
    (net (code "46") (name "Net-(U18-CLKOUT)") (class "Default")
      (node (ref "R153") (pin "2") (pinfunction "2_2") (pintype "passive"))
      (node (ref "U18") (pin "35") (pinfunction "CLKOUT_35") (pintype "output"))
    )
    (net (code "47") (name "Net-(U18-LED2_CFG_LDO1)") (class "Default")
      (node (ref "LD3") (pin "1") (pintype "passive"))
      (node (ref "R67") (pin "2") (pinfunction "2_2") (pintype "passive"))
      (node (ref "U18") (pin "34") (pinfunction "LED2_CFG_LDO1_34") (pintype "output"))
    )
    (net (code "48") (name "Net-(U18-REG_OUT)") (class "Default")
      (node (ref "LE1") (pin "1") (pinfunction "1_1") (pintype "passive"))
      (node (ref "U18") (pin "30") (pinfunction "REG_OUT_30") (pintype "output"))
    )
    (net (code "49") (name "Net-(U18-RSET)") (class "Default")
      (node (ref "R155") (pin "1") (pinfunction "1_1") (pintype "passive"))
      (node (ref "U18") (pin "39") (pinfunction "RSET_39") (pintype "output"))
    )
    (net (code "50") (name "Net-(U18-RXCLK_PHYAD1)") (class "Default")
      (node (ref "R58") (pin "2") (pinfunction "2_2") (pintype "passive"))
      (node (ref "U18") (pin "27") (pinfunction "RXCLK_PHYAD1_27") (pintype "passive"))
    )
    (net (code "51") (name "Net-(U18-RXCTL_PHYAD2)") (class "Default")
      (node (ref "R59") (pin "2") (pinfunction "2_2") (pintype "passive"))
      (node (ref "U18") (pin "26") (pinfunction "RXCTL_PHYAD2_26") (pintype "passive"))
    )
    (net (code "52") (name "Net-(U18-RXD0_RXDLY)") (class "Default")
      (node (ref "R60") (pin "2") (pinfunction "2_2") (pintype "passive"))
      (node (ref "U18") (pin "25") (pinfunction "RXD0_RXDLY_25") (pintype "output"))
    )
    (net (code "53") (name "Net-(U18-RXD1_TXDLY)") (class "Default")
      (node (ref "R61") (pin "2") (pinfunction "2_2") (pintype "passive"))
      (node (ref "U18") (pin "24") (pinfunction "RXD1_TXDLY_24") (pintype "output"))
    )
    (net (code "54") (name "Net-(U18-RXD2_PLLOFF)") (class "Default")
      (node (ref "R62") (pin "2") (pinfunction "2_2") (pintype "passive"))
      (node (ref "U18") (pin "23") (pinfunction "RXD2_PLLOFF_23") (pintype "output"))
    )
    (net (code "55") (name "Net-(U18-RXD3_PHYAD0)") (class "Default")
      (node (ref "R63") (pin "2") (pinfunction "2_2") (pintype "passive"))
      (node (ref "U18") (pin "22") (pinfunction "RXD3_PHYAD0_22") (pintype "output"))
    )
    (net (code "56") (name "Net-(U18-XTAL_IN)") (class "Default")
      (node (ref "R64") (pin "2") (pinfunction "2_2") (pintype "passive"))
      (node (ref "R69") (pin "1") (pinfunction "1_1") (pintype "passive"))
      (node (ref "U18") (pin "36") (pinfunction "XTAL_IN_36") (pintype "input"))
    )
    (net (code "57") (name "Net-(U18-XTAL_OUT_EXT_CLK)") (class "Default")
      (node (ref "R68") (pin "2") (pinfunction "2_2") (pintype "passive"))
      (node (ref "U18") (pin "37") (pinfunction "XTAL_OUT_EXT_CLK_37") (pintype "output"))
    )
    (net (code "58") (name "unconnected-(X2-Pad2)") (class "Default")
      (node (ref "X2") (pin "2") (pinfunction "2_2") (pintype "passive+no_connect"))
    )
    (net (code "59") (name "unconnected-(X2-Pad4)") (class "Default")
      (node (ref "X2") (pin "4") (pinfunction "4_4") (pintype "passive+no_connect"))
    )
  )
)
